# adpd2211_mixer.net
KiCad netlist of a schematic drawn in EAGLE
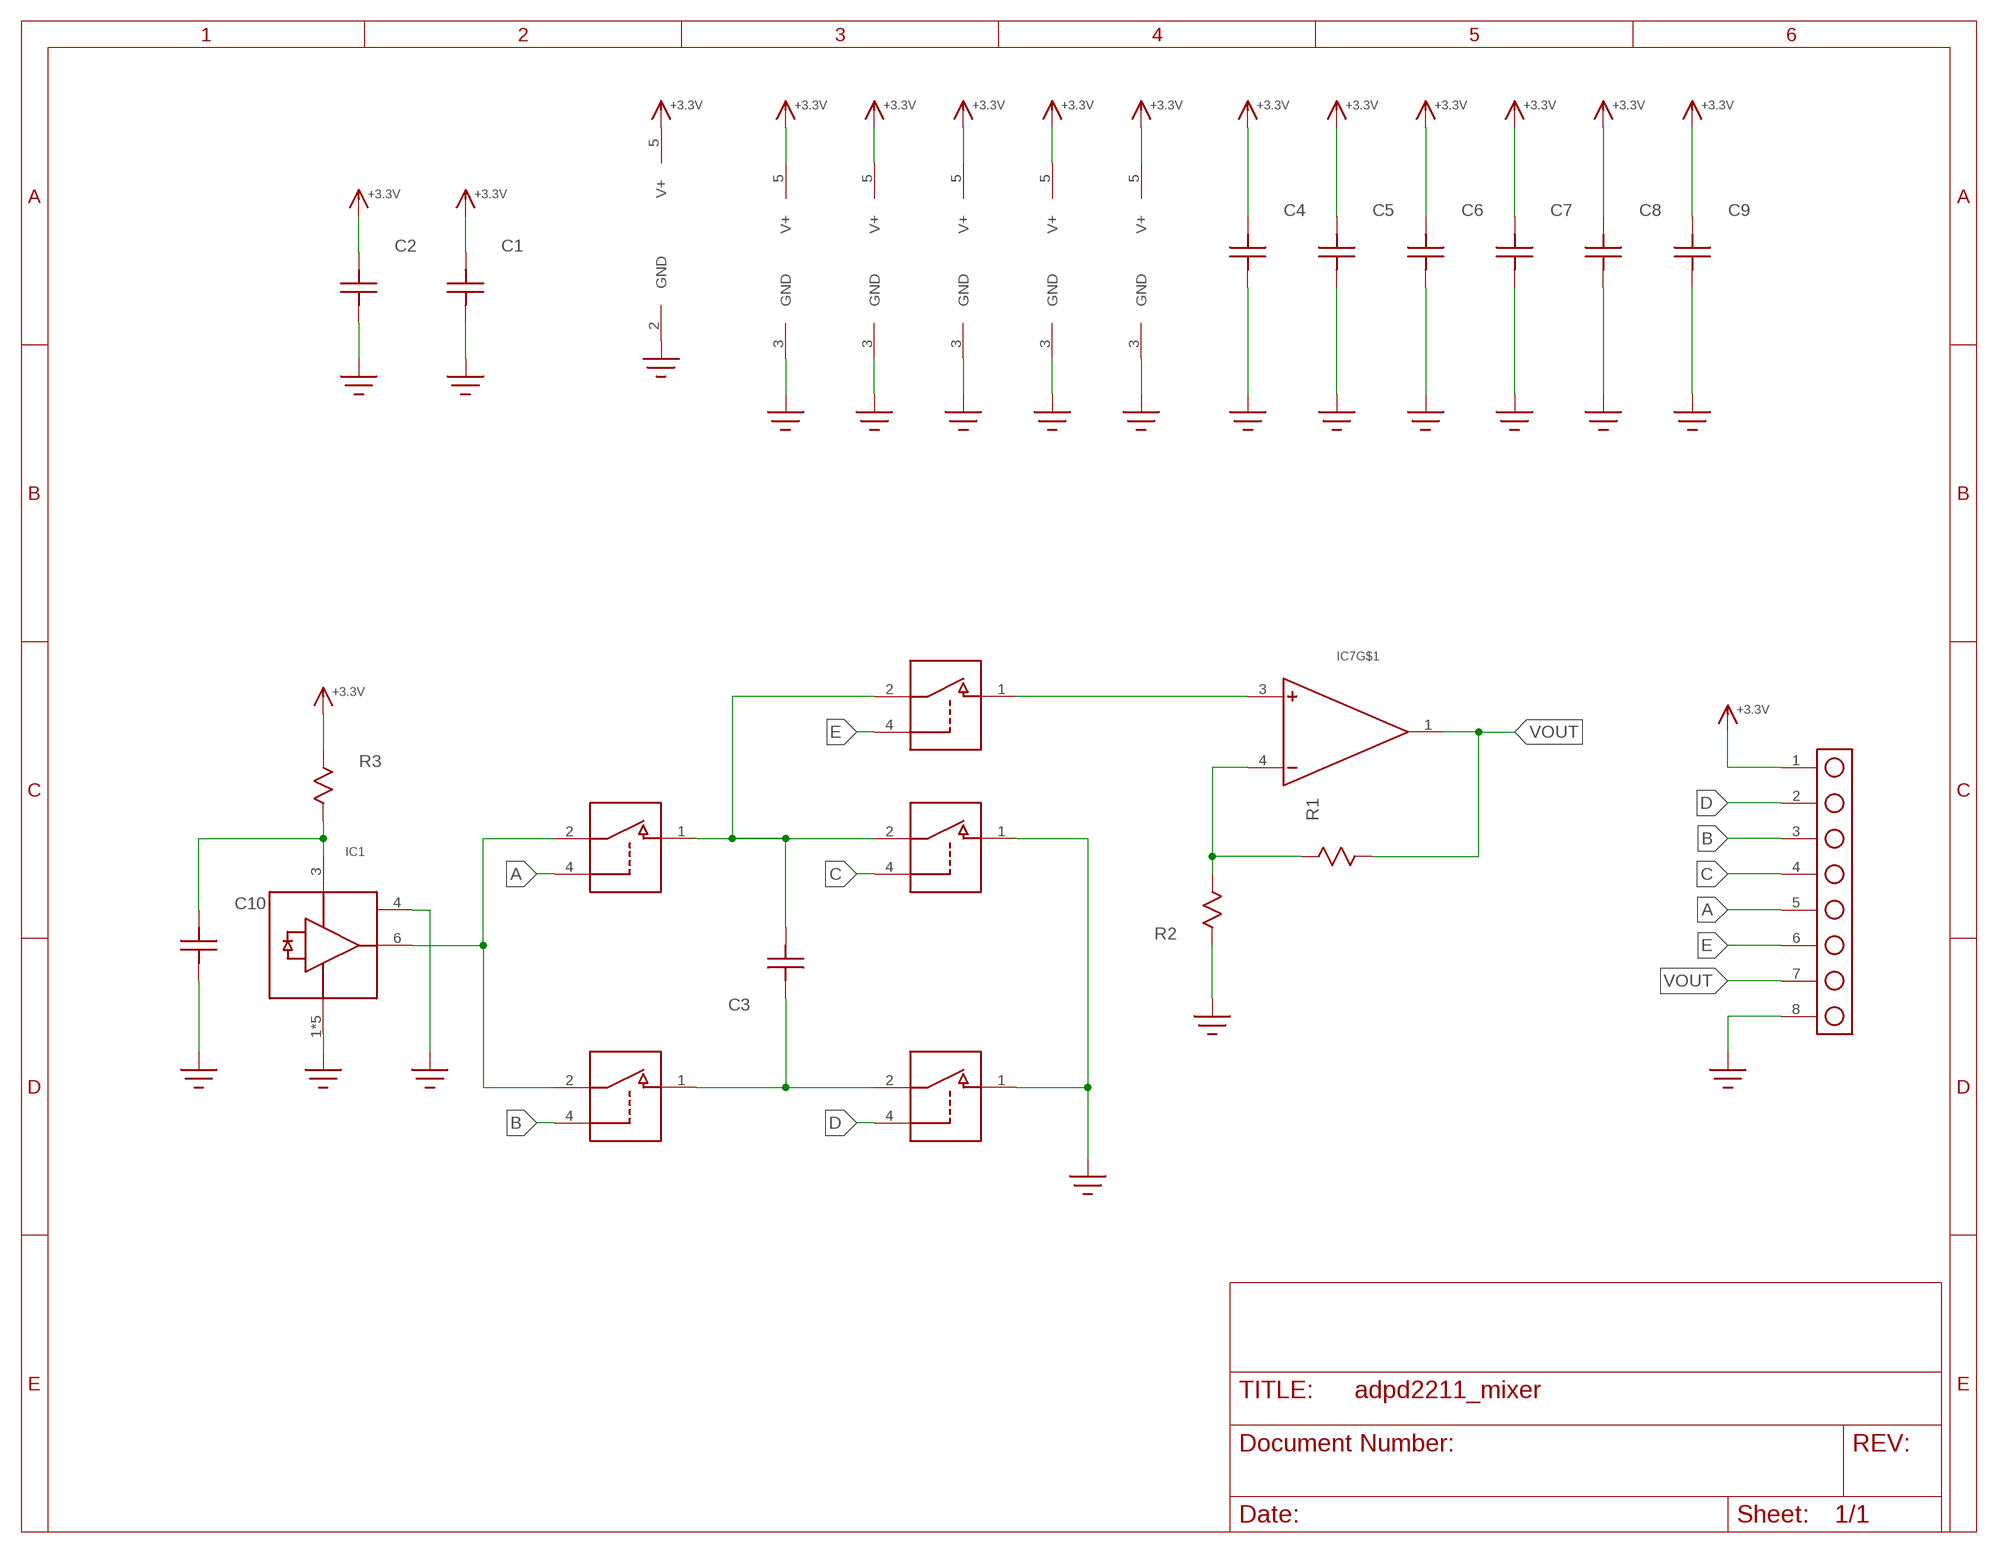
[diagram p0: schematic, sheet 1]

(export (version "E")
  (design (tool "Eeschema 10.0.6"))
  (components
    (comp (ref "C1")
      (value "C1206")
      (footprint "eagle-import:1206")
      (libsource (lib "eagle-import") (part "C1206"))
    )
    (comp (ref "C2")
      (value "C0603")
      (footprint "eagle-import:C0603")
      (libsource (lib "eagle-import") (part "C0603"))
    )
    (comp (ref "C3")
      (value "C0805")
      (footprint "eagle-import:0805")
      (libsource (lib "eagle-import") (part "C0805"))
    )
    (comp (ref "C4")
      (value "C0603")
      (footprint "eagle-import:C0603")
      (libsource (lib "eagle-import") (part "C0603"))
    )
    (comp (ref "C5")
      (value "C0603")
      (footprint "eagle-import:C0603")
      (libsource (lib "eagle-import") (part "C0603"))
    )
    (comp (ref "C6")
      (value "C0603")
      (footprint "eagle-import:C0603")
      (libsource (lib "eagle-import") (part "C0603"))
    )
    (comp (ref "C7")
      (value "C0603")
      (footprint "eagle-import:C0603")
      (libsource (lib "eagle-import") (part "C0603"))
    )
    (comp (ref "C8")
      (value "C0603")
      (footprint "eagle-import:C0603")
      (libsource (lib "eagle-import") (part "C0603"))
    )
    (comp (ref "C9")
      (value "C0603")
      (footprint "eagle-import:C0603")
      (libsource (lib "eagle-import") (part "C0603"))
    )
    (comp (ref "C10")
      (value "C0603")
      (footprint "eagle-import:C0603")
      (libsource (lib "eagle-import") (part "C0603"))
    )
    (comp (ref "IC1")
      (value "ADPD2211")
      (footprint "eagle-import:LFCSP8")
      (libsource (lib "eagle-import") (part "ADPD2211"))
    )
    (comp (ref "IC2")
      (value "TS5A3166")
      (footprint "eagle-import:SOT23-5")
      (libsource (lib "eagle-import") (part "TS5A3166"))
    )
    (comp (ref "IC3")
      (value "TS5A3166")
      (footprint "eagle-import:SOT23-5")
      (libsource (lib "eagle-import") (part "TS5A3166"))
    )
    (comp (ref "IC4")
      (value "TS5A3166")
      (footprint "eagle-import:SOT23-5")
      (libsource (lib "eagle-import") (part "TS5A3166"))
    )
    (comp (ref "IC5")
      (value "TS5A3166")
      (footprint "eagle-import:SOT23-5")
      (libsource (lib "eagle-import") (part "TS5A3166"))
    )
    (comp (ref "IC6")
      (value "TS5A3166")
      (footprint "eagle-import:SOT23-5")
      (libsource (lib "eagle-import") (part "TS5A3166"))
    )
    (comp (ref "IC7")
      (value "AD8538")
      (footprint "eagle-import:SOT23-5")
      (libsource (lib "eagle-import") (part "AD8538"))
    )
    (comp (ref "J1")
      (value "HEADER_8_PIN")
      (footprint "eagle-import:HEADER_8_PIN")
      (libsource (lib "eagle-import") (part "HEADER_8_PIN"))
    )
    (comp (ref "R1")
      (value "R0603")
      (footprint "eagle-import:R0603")
      (libsource (lib "eagle-import") (part "R0603"))
    )
    (comp (ref "R2")
      (value "R0603")
      (footprint "eagle-import:R0603")
      (libsource (lib "eagle-import") (part "R0603"))
    )
    (comp (ref "R3")
      (value "R0603")
      (footprint "eagle-import:R0603")
      (libsource (lib "eagle-import") (part "R0603"))
    )
  )
  (nets
    (net (code "1") (name "+3.3V") (class "Default")
      (node (ref "C1") (pin "P$2") (pinfunction "P$2_P$2") (pintype "bidirectional"))
      (node (ref "C2") (pin "P$2") (pinfunction "P$2_P$2") (pintype "bidirectional"))
      (node (ref "C4") (pin "P$2") (pinfunction "P$2_P$2") (pintype "bidirectional"))
      (node (ref "C5") (pin "P$2") (pinfunction "P$2_P$2") (pintype "bidirectional"))
      (node (ref "C6") (pin "P$2") (pinfunction "P$2_P$2") (pintype "bidirectional"))
      (node (ref "C7") (pin "P$2") (pinfunction "P$2_P$2") (pintype "bidirectional"))
      (node (ref "C8") (pin "P$2") (pinfunction "P$2_P$2") (pintype "bidirectional"))
      (node (ref "C9") (pin "P$2") (pinfunction "P$2_P$2") (pintype "bidirectional"))
      (node (ref "IC2") (pin "5") (pinfunction "V+_5") (pintype "bidirectional"))
      (node (ref "IC3") (pin "5") (pinfunction "V+_5") (pintype "bidirectional"))
      (node (ref "IC4") (pin "5") (pinfunction "V+_5") (pintype "bidirectional"))
      (node (ref "IC5") (pin "5") (pinfunction "V+_5") (pintype "bidirectional"))
      (node (ref "IC6") (pin "5") (pinfunction "V+_5") (pintype "bidirectional"))
      (node (ref "IC7") (pin "5") (pinfunction "V+_5") (pintype "bidirectional"))
      (node (ref "J1") (pin "1") (pinfunction "1_1") (pintype "bidirectional"))
      (node (ref "R3") (pin "P$1") (pinfunction "P$3_P$1") (pintype "bidirectional"))
    )
    (net (code "2") (name "A") (class "Default")
      (node (ref "IC2") (pin "4") (pinfunction "IN_4") (pintype "bidirectional"))
      (node (ref "J1") (pin "5") (pinfunction "5_5") (pintype "bidirectional"))
    )
    (net (code "3") (name "B") (class "Default")
      (node (ref "IC4") (pin "4") (pinfunction "IN_4") (pintype "bidirectional"))
      (node (ref "J1") (pin "3") (pinfunction "3_3") (pintype "bidirectional"))
    )
    (net (code "4") (name "C") (class "Default")
      (node (ref "IC3") (pin "4") (pinfunction "IN_4") (pintype "bidirectional"))
      (node (ref "J1") (pin "4") (pinfunction "4_4") (pintype "bidirectional"))
    )
    (net (code "5") (name "D") (class "Default")
      (node (ref "IC5") (pin "4") (pinfunction "IN_4") (pintype "bidirectional"))
      (node (ref "J1") (pin "2") (pinfunction "2_2") (pintype "bidirectional"))
    )
    (net (code "6") (name "E") (class "Default")
      (node (ref "IC6") (pin "4") (pinfunction "IN_4") (pintype "bidirectional"))
      (node (ref "J1") (pin "6") (pinfunction "6_6") (pintype "bidirectional"))
    )
    (net (code "7") (name "GND") (class "Default")
      (node (ref "C1") (pin "P$1") (pinfunction "P$1_P$1") (pintype "bidirectional"))
      (node (ref "C10") (pin "P$1") (pinfunction "P$1_P$1") (pintype "bidirectional"))
      (node (ref "C2") (pin "P$1") (pinfunction "P$1_P$1") (pintype "bidirectional"))
      (node (ref "C4") (pin "P$1") (pinfunction "P$1_P$1") (pintype "bidirectional"))
      (node (ref "C5") (pin "P$1") (pinfunction "P$1_P$1") (pintype "bidirectional"))
      (node (ref "C6") (pin "P$1") (pinfunction "P$1_P$1") (pintype "bidirectional"))
      (node (ref "C7") (pin "P$1") (pinfunction "P$1_P$1") (pintype "bidirectional"))
      (node (ref "C8") (pin "P$1") (pinfunction "P$1_P$1") (pintype "bidirectional"))
      (node (ref "C9") (pin "P$1") (pinfunction "P$1_P$1") (pintype "bidirectional"))
      (node (ref "IC1") (pin "1") (pinfunction "GND_1") (pintype "bidirectional"))
      (node (ref "IC1") (pin "2") (pinfunction "GND_2") (pintype "bidirectional"))
      (node (ref "IC1") (pin "4") (pinfunction "PWDN_4") (pintype "bidirectional"))
      (node (ref "IC1") (pin "5") (pinfunction "GND_5") (pintype "bidirectional"))
      (node (ref "IC1") (pin "7") (pinfunction "GND_7") (pintype "bidirectional"))
      (node (ref "IC1") (pin "8") (pinfunction "GND_8") (pintype "bidirectional"))
      (node (ref "IC2") (pin "3") (pinfunction "GND_3") (pintype "bidirectional"))
      (node (ref "IC3") (pin "1") (pinfunction "NO_1") (pintype "bidirectional"))
      (node (ref "IC3") (pin "3") (pinfunction "GND_3") (pintype "bidirectional"))
      (node (ref "IC4") (pin "3") (pinfunction "GND_3") (pintype "bidirectional"))
      (node (ref "IC5") (pin "1") (pinfunction "NO_1") (pintype "bidirectional"))
      (node (ref "IC5") (pin "3") (pinfunction "GND_3") (pintype "bidirectional"))
      (node (ref "IC6") (pin "3") (pinfunction "GND_3") (pintype "bidirectional"))
      (node (ref "IC7") (pin "2") (pinfunction "GND_2") (pintype "bidirectional"))
      (node (ref "J1") (pin "8") (pinfunction "8_8") (pintype "bidirectional"))
      (node (ref "R2") (pin "P$1") (pinfunction "P$3_P$1") (pintype "bidirectional"))
    )
    (net (code "8") (name "Net-(IC1-OUT)") (class "Default")
      (node (ref "IC1") (pin "6") (pinfunction "OUT_6") (pintype "bidirectional"))
      (node (ref "IC2") (pin "2") (pinfunction "COM_2") (pintype "bidirectional"))
      (node (ref "IC4") (pin "2") (pinfunction "COM_2") (pintype "bidirectional"))
    )
    (net (code "9") (name "Net-(IC1-VCC)") (class "Default")
      (node (ref "C10") (pin "P$2") (pinfunction "P$2_P$2") (pintype "bidirectional"))
      (node (ref "IC1") (pin "3") (pinfunction "VCC_3") (pintype "bidirectional"))
      (node (ref "R3") (pin "P$2") (pinfunction "P$4_P$2") (pintype "bidirectional"))
    )
    (net (code "10") (name "Net-(IC2A-NO)") (class "Default")
      (node (ref "C3") (pin "P$1") (pinfunction "P$1_P$1") (pintype "bidirectional"))
      (node (ref "IC2") (pin "1") (pinfunction "NO_1") (pintype "bidirectional"))
      (node (ref "IC3") (pin "2") (pinfunction "COM_2") (pintype "bidirectional"))
      (node (ref "IC6") (pin "2") (pinfunction "COM_2") (pintype "bidirectional"))
    )
    (net (code "11") (name "Net-(IC4A-NO)") (class "Default")
      (node (ref "C3") (pin "P$2") (pinfunction "P$2_P$2") (pintype "bidirectional"))
      (node (ref "IC4") (pin "1") (pinfunction "NO_1") (pintype "bidirectional"))
      (node (ref "IC5") (pin "2") (pinfunction "COM_2") (pintype "bidirectional"))
    )
    (net (code "12") (name "Net-(IC6A-NO)") (class "Default")
      (node (ref "IC6") (pin "1") (pinfunction "NO_1") (pintype "bidirectional"))
      (node (ref "IC7") (pin "3") (pinfunction "+_3") (pintype "bidirectional"))
    )
    (net (code "13") (name "Net-(IC7A--)") (class "Default")
      (node (ref "IC7") (pin "4") (pinfunction "-_4") (pintype "bidirectional"))
      (node (ref "R1") (pin "P$1") (pinfunction "P$3_P$1") (pintype "bidirectional"))
      (node (ref "R2") (pin "P$2") (pinfunction "P$4_P$2") (pintype "bidirectional"))
    )
    (net (code "14") (name "VOUT") (class "Default")
      (node (ref "IC7") (pin "1") (pinfunction "OUT_1") (pintype "bidirectional"))
      (node (ref "J1") (pin "7") (pinfunction "7_7") (pintype "bidirectional"))
      (node (ref "R1") (pin "P$2") (pinfunction "P$4_P$2") (pintype "bidirectional"))
    )
  )
)
